# 17-RESET_GENERATION.net
KiCad netlist of a schematic drawn in Altium Designer
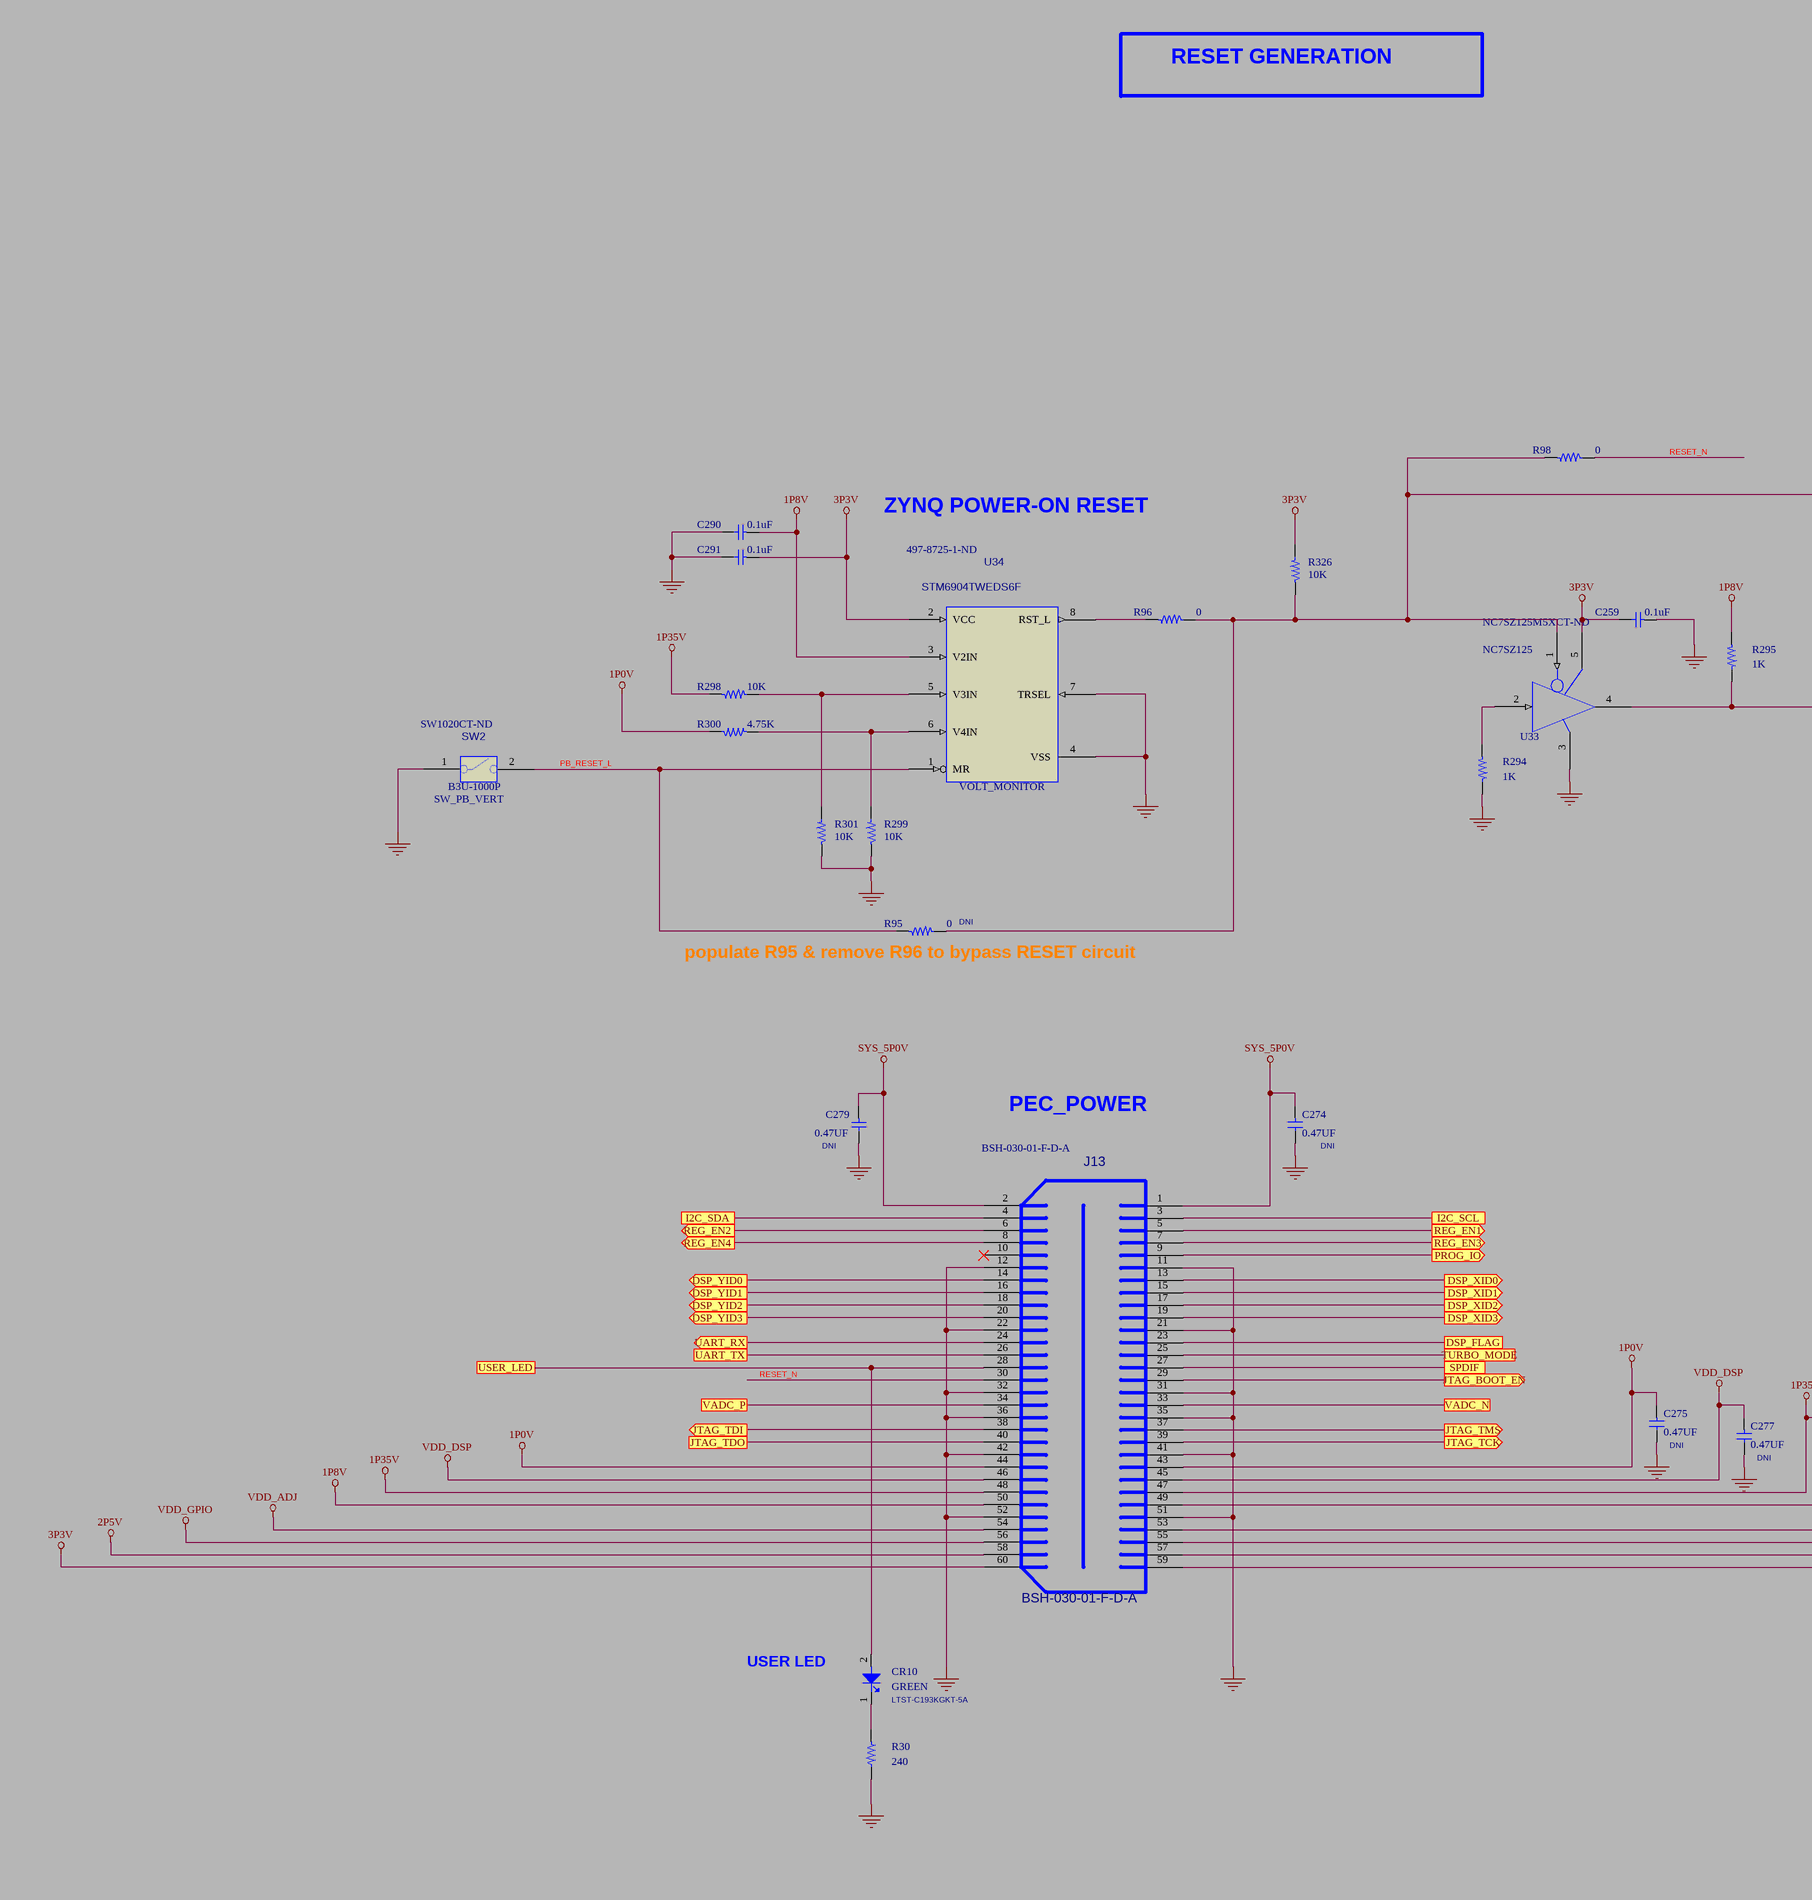
[diagram p0: 17-RESET GENERATION.SchDoc, left]
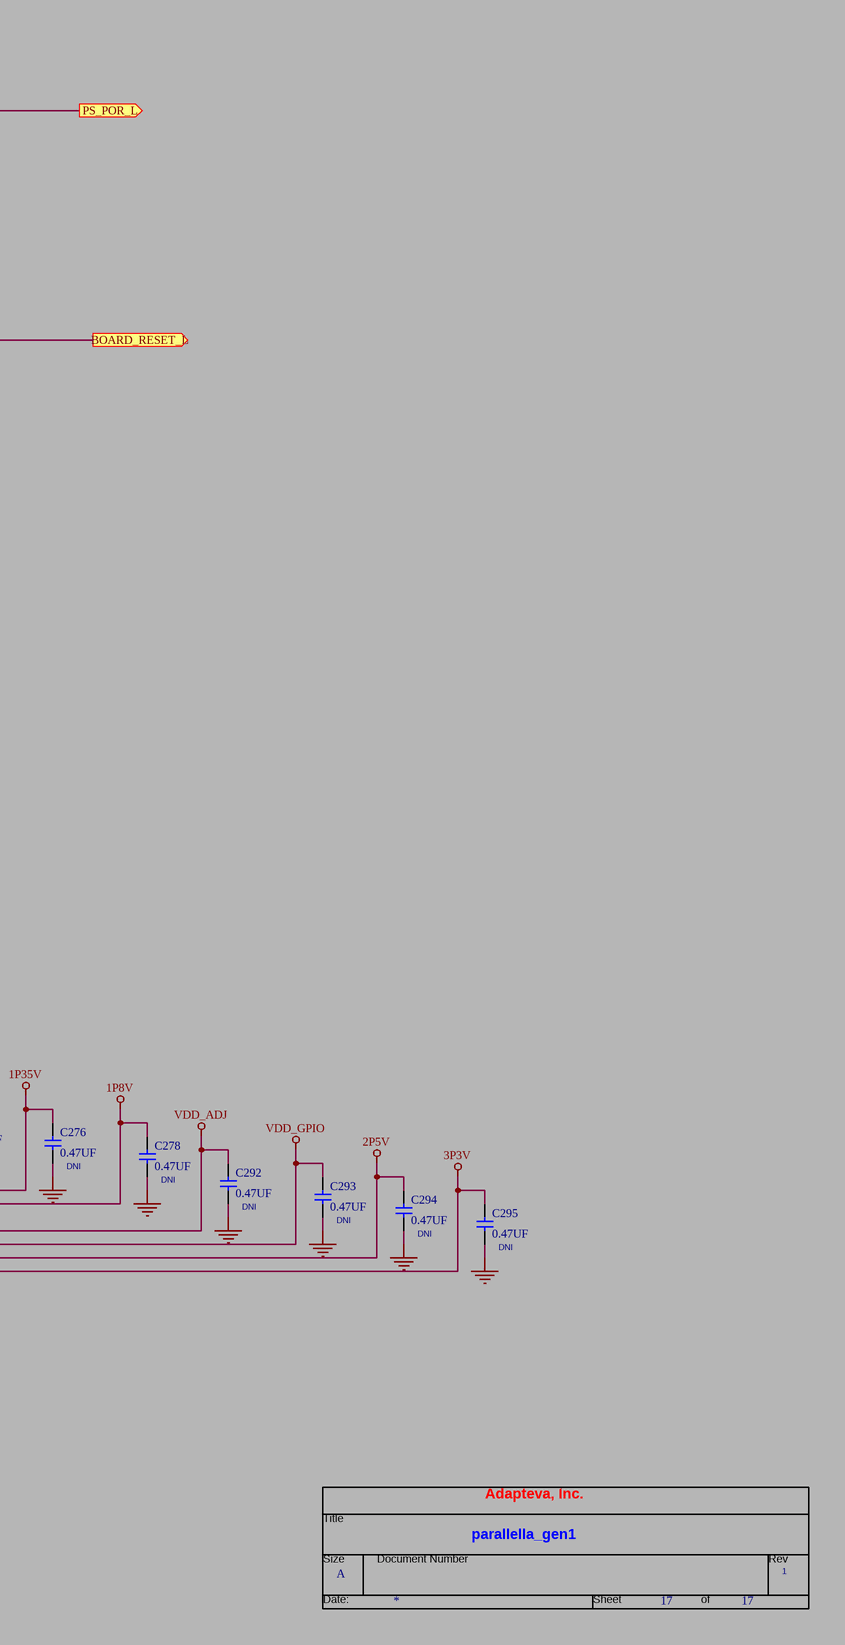
[diagram p1: 17-RESET GENERATION.SchDoc, right]

(export (version "E")
  (design (tool "Eeschema 10.0.6"))
  (components
    (comp (ref "C259")
      (value "0.1uF")
      (footprint "C0402")
      (description "CAP, 0402, 0.1UF, X5R, 35V")
      (fields (field (name "MFG PART NO") "GMK105BJ104KV-F") (field (name "MFG") "TAIYO YUDEN"))
      (libsource (lib "*") (part "CAP0402_0P1UF_X5R_35V"))
    )
    (comp (ref "C274")
      (value "0.47UF")
      (footprint "C0402")
      (description "CAP, 0402, 0.47UF, X5R, 16V")
      (fields
        (field (name "MFG") "TDK")
        (field (name "MFG PART NO") "C1005X5R1C474K")
        (field (name "INSTALL") "DNI")
      )
      (libsource (lib "*") (part "CAP0402_0P47UF_X5R"))
    )
    (comp (ref "C275")
      (value "0.47UF")
      (footprint "C0402")
      (description "CAP, 0402, 0.47UF, X5R, 16V")
      (fields
        (field (name "MFG") "TDK")
        (field (name "MFG PART NO") "C1005X5R1C474K")
        (field (name "INSTALL") "DNI")
      )
      (libsource (lib "*") (part "CAP0402_0P47UF_X5R"))
    )
    (comp (ref "C276")
      (value "0.47UF")
      (footprint "C0402")
      (description "CAP, 0402, 0.47UF, X5R, 16V")
      (fields
        (field (name "MFG") "TDK")
        (field (name "MFG PART NO") "C1005X5R1C474K")
        (field (name "INSTALL") "DNI")
      )
      (libsource (lib "*") (part "CAP0402_0P47UF_X5R"))
    )
    (comp (ref "C277")
      (value "0.47UF")
      (footprint "C0402")
      (description "CAP, 0402, 0.47UF, X5R, 16V")
      (fields
        (field (name "MFG") "TDK")
        (field (name "MFG PART NO") "C1005X5R1C474K")
        (field (name "INSTALL") "DNI")
      )
      (libsource (lib "*") (part "CAP0402_0P47UF_X5R"))
    )
    (comp (ref "C278")
      (value "0.47UF")
      (footprint "C0402")
      (description "CAP, 0402, 0.47UF, X5R, 16V")
      (fields
        (field (name "MFG") "TDK")
        (field (name "MFG PART NO") "C1005X5R1C474K")
        (field (name "INSTALL") "DNI")
      )
      (libsource (lib "*") (part "CAP0402_0P47UF_X5R"))
    )
    (comp (ref "C279")
      (value "0.47UF")
      (footprint "C0402")
      (description "CAP, 0402, 0.47UF, X5R, 16V")
      (fields
        (field (name "MFG") "TDK")
        (field (name "MFG PART NO") "C1005X5R1C474K")
        (field (name "INSTALL") "DNI")
      )
      (libsource (lib "*") (part "CAP0402_0P47UF_X5R"))
    )
    (comp (ref "C290")
      (value "0.1uF")
      (footprint "C0402")
      (description "CAP, 0402, 0.1UF, X5R, 35V")
      (fields (field (name "MFG PART NO") "GMK105BJ104KV-F") (field (name "MFG") "TAIYO YUDEN"))
      (libsource (lib "*") (part "CAP0402_0P1UF_X5R_35V"))
    )
    (comp (ref "C291")
      (value "0.1uF")
      (footprint "C0402")
      (description "CAP, 0402, 0.1UF, X5R, 35V")
      (fields (field (name "MFG PART NO") "GMK105BJ104KV-F") (field (name "MFG") "TAIYO YUDEN"))
      (libsource (lib "*") (part "CAP0402_0P1UF_X5R_35V"))
    )
    (comp (ref "C292")
      (value "0.47UF")
      (footprint "C0402")
      (description "CAP, 0402, 0.47UF, X5R, 16V")
      (fields
        (field (name "MFG") "TDK")
        (field (name "MFG PART NO") "C1005X5R1C474K")
        (field (name "INSTALL") "DNI")
      )
      (libsource (lib "*") (part "CAP0402_0P47UF_X5R"))
    )
    (comp (ref "C293")
      (value "0.47UF")
      (footprint "C0402")
      (description "CAP, 0402, 0.47UF, X5R, 16V")
      (fields
        (field (name "MFG") "TDK")
        (field (name "MFG PART NO") "C1005X5R1C474K")
        (field (name "INSTALL") "DNI")
      )
      (libsource (lib "*") (part "CAP0402_0P47UF_X5R"))
    )
    (comp (ref "C294")
      (value "0.47UF")
      (footprint "C0402")
      (description "CAP, 0402, 0.47UF, X5R, 16V")
      (fields
        (field (name "MFG") "TDK")
        (field (name "MFG PART NO") "C1005X5R1C474K")
        (field (name "INSTALL") "DNI")
      )
      (libsource (lib "*") (part "CAP0402_0P47UF_X5R"))
    )
    (comp (ref "C295")
      (value "0.47UF")
      (footprint "C0402")
      (description "CAP, 0402, 0.47UF, X5R, 16V")
      (fields
        (field (name "MFG") "TDK")
        (field (name "MFG PART NO") "C1005X5R1C474K")
        (field (name "INSTALL") "DNI")
      )
      (libsource (lib "*") (part "CAP0402_0P47UF_X5R"))
    )
    (comp (ref "CR10")
      (value "GREEN")
      (footprint "LED_0603")
      (description "LED, 0603, 5MA, SMT, GREEN")
      (fields
        (field (name "VOLTAGE") "2V")
        (field (name "MFG") "LITE-ON INC")
        (field (name "VENDOR PN") "LTST-C193KGKT-5A")
      )
      (libsource (lib "*") (part "LED_0603_5MA_GRN"))
    )
    (comp (ref "J13")
      (value "BSH-030-01-F-D-A")
      (footprint "CONN_BSH60P_13P59X25P88_P5P_V")
      (fields (field (name "SUPPLIER PART NUMBER 1") "BSH-030-01-F-D-A"))
      (libsource (lib "*") (part "CON_BSH_030_VERT"))
    )
    (comp (ref "R30")
      (value "240")
      (footprint "R0402")
      (description "RES, 0402, 240, 1%")
      (fields (field (name "MFG") "VISHAY") (field (name "MFG PART NO") "CRCW0402240RFKED"))
      (libsource (lib "*") (part "RES0402_240"))
    )
    (comp (ref "R95")
      (value "0")
      (footprint "R0402")
      (description "RES, 0402, 0 OHM, 1%")
      (fields
        (field (name "MFG") "VISHAY")
        (field (name "MFG PART NO") "CRCW04020000Z0ED")
        (field (name "INSTALL") "DNI")
      )
      (libsource (lib "*") (part "RES0402_0"))
    )
    (comp (ref "R96")
      (value "0")
      (footprint "R0402")
      (description "RES, 0402, 0 OHM, 1%")
      (fields (field (name "MFG") "VISHAY") (field (name "MFG PART NO") "CRCW04020000Z0ED"))
      (libsource (lib "*") (part "RES0402_0"))
    )
    (comp (ref "R98")
      (value "0")
      (footprint "R0402")
      (description "RES, 0402, 0 OHM, 1%")
      (fields (field (name "MFG") "VISHAY") (field (name "MFG PART NO") "CRCW04020000Z0ED"))
      (libsource (lib "*") (part "RES0402_0"))
    )
    (comp (ref "R294")
      (value "1K")
      (footprint "R0402")
      (description "RES, 0402, 1K")
      (fields (field (name "MFG") "VISHAY") (field (name "MFG PART NO") "CRCW04021K00FKED"))
      (libsource (lib "*") (part "RES0402_1K"))
    )
    (comp (ref "R295")
      (value "1K")
      (footprint "R0402")
      (description "RES, 0402, 1K")
      (fields (field (name "MFG") "VISHAY") (field (name "MFG PART NO") "CRCW04021K00FKED"))
      (libsource (lib "*") (part "RES0402_1K"))
    )
    (comp (ref "R298")
      (value "10K")
      (footprint "R0402")
      (description "RES, 0402, 10K")
      (fields (field (name "MFG") "VISHAY") (field (name "MFG PART NO") "CRCW040210K0FKED"))
      (libsource (lib "*") (part "RES0402_10K"))
    )
    (comp (ref "R299")
      (value "10K")
      (footprint "R0402")
      (description "RES, 0402, 10K")
      (fields (field (name "MFG") "VISHAY") (field (name "MFG PART NO") "CRCW040210K0FKED"))
      (libsource (lib "*") (part "RES0402_10K"))
    )
    (comp (ref "R300")
      (value "4.75K")
      (footprint "R0402")
      (description "RES, 0402, 4.75K, 1%")
      (fields (field (name "MFG") "VISHAY") (field (name "MFG PART NO") "CRCW04024K75FKED"))
      (libsource (lib "*") (part "RES0402_4K75"))
    )
    (comp (ref "R301")
      (value "10K")
      (footprint "R0402")
      (description "RES, 0402, 10K")
      (fields (field (name "MFG") "VISHAY") (field (name "MFG PART NO") "CRCW040210K0FKED"))
      (libsource (lib "*") (part "RES0402_10K"))
    )
    (comp (ref "R326")
      (value "10K")
      (footprint "R0402")
      (description "RES, 0402, 10K")
      (fields (field (name "MFG") "VISHAY") (field (name "MFG PART NO") "CRCW040210K0FKED"))
      (libsource (lib "*") (part "RES0402_10K"))
    )
    (comp (ref "SW2")
      (value "SW_PB_VERT")
      (footprint "SWITCH_2P5X4X1P6MMH")
      (description "SW, PUSHBUTTON, SPST, NORMALLY OPEN, SMT")
      (fields (field (name "VENDOR PN") "B3U-1000P") (field (name "SUPPLIER PART NUMBER 1") "SW1020CT-ND"))
      (libsource (lib "*") (part "SW_PB_SPST_2PIN"))
    )
    (comp (ref "U33")
      (value "NC7SZ125")
      (footprint "SOT_5PIN")
      (fields
        (field (name "PART_NUMBER") "XXX-XXXXX-XX")
        (field (name "MFG") "FAIRCHILD")
        (field (name "MFG PART NO") "NC7SZ125M5X")
        (field (name "SUPPLIER PART NUMBER 1") "NC7SZ125M5XCT-ND")
      )
      (libsource (lib "*") (part "NC7SZ125"))
    )
    (comp (ref "U34")
      (value "VOLT_MONITOR")
      (footprint "TSSOP8_3SQX1P1H_P65P")
      (description "IC,  SUPPLY MONITOR, 4 INPUTS, TSSOP8")
      (fields
        (field (name "MFG PART NO") "STM6904TWEDS6F")
        (field (name "MFG") "ST MICROELECTRONICS")
        (field (name "SUPPLIER PART NUMBER 1") "497-8725-1-ND")
      )
      (libsource (lib "*") (part "VOLTMON_4IN_3P3"))
    )
  )
  (nets
    (net (code "1") (name "/BOARD_RESET_L") (class "Default")
      (node (ref "R295") (pin "2") (pinfunction "2_2") (pintype "passive"))
      (node (ref "U33") (pin "4") (pinfunction "Y_4") (pintype "tri_state"))
    )
    (net (code "2") (name "/DSP_FLAG") (class "Default")
      (node (ref "J13") (pin "23") (pinfunction "23_23") (pintype "passive"))
    )
    (net (code "3") (name "/DSP_XID0") (class "Default")
      (node (ref "J13") (pin "13") (pinfunction "13_13") (pintype "passive"))
    )
    (net (code "4") (name "/DSP_XID1") (class "Default")
      (node (ref "J13") (pin "15") (pinfunction "15_15") (pintype "passive"))
    )
    (net (code "5") (name "/DSP_XID2") (class "Default")
      (node (ref "J13") (pin "17") (pinfunction "17_17") (pintype "passive"))
    )
    (net (code "6") (name "/DSP_XID3") (class "Default")
      (node (ref "J13") (pin "19") (pinfunction "19_19") (pintype "passive"))
    )
    (net (code "7") (name "/DSP_YID0") (class "Default")
      (node (ref "J13") (pin "14") (pinfunction "14_14") (pintype "passive"))
    )
    (net (code "8") (name "/DSP_YID1") (class "Default")
      (node (ref "J13") (pin "16") (pinfunction "16_16") (pintype "passive"))
    )
    (net (code "9") (name "/DSP_YID2") (class "Default")
      (node (ref "J13") (pin "18") (pinfunction "18_18") (pintype "passive"))
    )
    (net (code "10") (name "/DSP_YID3") (class "Default")
      (node (ref "J13") (pin "20") (pinfunction "20_20") (pintype "passive"))
    )
    (net (code "11") (name "/I2C_SCL") (class "Default")
      (node (ref "J13") (pin "3") (pinfunction "03_3") (pintype "passive"))
    )
    (net (code "12") (name "/I2C_SDA") (class "Default")
      (node (ref "J13") (pin "4") (pinfunction "04_4") (pintype "passive"))
    )
    (net (code "13") (name "/JTAG_BOOT_EN") (class "Default")
      (node (ref "J13") (pin "29") (pinfunction "29_29") (pintype "passive"))
    )
    (net (code "14") (name "/JTAG_TCK") (class "Default")
      (node (ref "J13") (pin "39") (pinfunction "39_39") (pintype "passive"))
    )
    (net (code "15") (name "/JTAG_TDI") (class "Default")
      (node (ref "J13") (pin "38") (pinfunction "38_38") (pintype "passive"))
    )
    (net (code "16") (name "/JTAG_TDO") (class "Default")
      (node (ref "J13") (pin "40") (pinfunction "40_40") (pintype "passive"))
    )
    (net (code "17") (name "/JTAG_TMS") (class "Default")
      (node (ref "J13") (pin "37") (pinfunction "37_37") (pintype "passive"))
    )
    (net (code "18") (name "/PB_RESET_L") (class "Default")
      (node (ref "R95") (pin "1") (pinfunction "1_1") (pintype "passive"))
      (node (ref "SW2") (pin "2") (pinfunction "B_2") (pintype "passive"))
      (node (ref "U34") (pin "1") (pinfunction "MR_1") (pintype "input"))
    )
    (net (code "19") (name "/PROG_IO") (class "Default")
      (node (ref "J13") (pin "9") (pinfunction "09_9") (pintype "passive"))
    )
    (net (code "20") (name "/PS_POR_L") (class "Default")
      (node (ref "R326") (pin "1") (pinfunction "1_1") (pintype "passive"))
      (node (ref "R95") (pin "2") (pinfunction "2_2") (pintype "passive"))
      (node (ref "R96") (pin "2") (pinfunction "2_2") (pintype "passive"))
      (node (ref "R98") (pin "1") (pinfunction "1_1") (pintype "passive"))
      (node (ref "U33") (pin "1") (pinfunction "~{OE}_1") (pintype "input"))
    )
    (net (code "21") (name "/REG_EN1") (class "Default")
      (node (ref "J13") (pin "5") (pinfunction "05_5") (pintype "passive"))
    )
    (net (code "22") (name "/REG_EN2") (class "Default")
      (node (ref "J13") (pin "6") (pinfunction "06_6") (pintype "passive"))
    )
    (net (code "23") (name "/REG_EN3") (class "Default")
      (node (ref "J13") (pin "7") (pinfunction "07_7") (pintype "passive"))
    )
    (net (code "24") (name "/REG_EN4") (class "Default")
      (node (ref "J13") (pin "8") (pinfunction "08_8") (pintype "passive"))
    )
    (net (code "25") (name "/RESET_N") (class "Default")
      (node (ref "J13") (pin "30") (pinfunction "30_30") (pintype "passive"))
      (node (ref "R98") (pin "2") (pinfunction "2_2") (pintype "passive"))
    )
    (net (code "26") (name "/SPDIF") (class "Default")
      (node (ref "J13") (pin "27") (pinfunction "27_27") (pintype "passive"))
    )
    (net (code "27") (name "/TURBO_MODE") (class "Default")
      (node (ref "J13") (pin "25") (pinfunction "25_25") (pintype "passive"))
    )
    (net (code "28") (name "/UART_RX") (class "Default")
      (node (ref "J13") (pin "24") (pinfunction "24_24") (pintype "passive"))
    )
    (net (code "29") (name "/UART_TX") (class "Default")
      (node (ref "J13") (pin "26") (pinfunction "26_26") (pintype "passive"))
    )
    (net (code "30") (name "/USER_LED") (class "Default")
      (node (ref "CR10") (pin "2") (pinfunction "A_2") (pintype "passive"))
      (node (ref "J13") (pin "28") (pinfunction "28_28") (pintype "passive"))
    )
    (net (code "31") (name "/VADC_N") (class "Default")
      (node (ref "J13") (pin "33") (pinfunction "33_33") (pintype "passive"))
    )
    (net (code "32") (name "/VADC_P") (class "Default")
      (node (ref "J13") (pin "34") (pinfunction "34_34") (pintype "passive"))
    )
    (net (code "33") (name "1P0V") (class "Default")
      (node (ref "C275") (pin "1") (pinfunction "1_1") (pintype "passive"))
      (node (ref "J13") (pin "43") (pinfunction "43_43") (pintype "passive"))
      (node (ref "J13") (pin "44") (pinfunction "44_44") (pintype "passive"))
      (node (ref "R300") (pin "2") (pinfunction "2_2") (pintype "passive"))
    )
    (net (code "34") (name "1P8V") (class "Default")
      (node (ref "C278") (pin "1") (pinfunction "1_1") (pintype "passive"))
      (node (ref "C290") (pin "1") (pinfunction "1_1") (pintype "passive"))
      (node (ref "J13") (pin "49") (pinfunction "49_49") (pintype "passive"))
      (node (ref "J13") (pin "50") (pinfunction "50_50") (pintype "passive"))
      (node (ref "R295") (pin "1") (pinfunction "1_1") (pintype "passive"))
      (node (ref "U34") (pin "3") (pinfunction "V2IN_3") (pintype "input"))
    )
    (net (code "35") (name "1P35V") (class "Default")
      (node (ref "C276") (pin "1") (pinfunction "1_1") (pintype "passive"))
      (node (ref "J13") (pin "47") (pinfunction "47_47") (pintype "passive"))
      (node (ref "J13") (pin "48") (pinfunction "48_48") (pintype "passive"))
      (node (ref "R298") (pin "1") (pinfunction "1_1") (pintype "passive"))
    )
    (net (code "36") (name "2P5V") (class "Default")
      (node (ref "C294") (pin "1") (pinfunction "1_1") (pintype "passive"))
      (node (ref "J13") (pin "57") (pinfunction "57_57") (pintype "passive"))
      (node (ref "J13") (pin "58") (pinfunction "58_58") (pintype "passive"))
    )
    (net (code "37") (name "3P3V") (class "Default")
      (node (ref "C259") (pin "2") (pinfunction "2_2") (pintype "passive"))
      (node (ref "C291") (pin "1") (pinfunction "1_1") (pintype "passive"))
      (node (ref "C295") (pin "1") (pinfunction "1_1") (pintype "passive"))
      (node (ref "J13") (pin "59") (pinfunction "59_59") (pintype "passive"))
      (node (ref "J13") (pin "60") (pinfunction "60_60") (pintype "passive"))
      (node (ref "R326") (pin "2") (pinfunction "2_2") (pintype "passive"))
      (node (ref "U33") (pin "5") (pinfunction "VCC_5") (pintype "passive"))
      (node (ref "U34") (pin "2") (pinfunction "VCC_2") (pintype "input"))
    )
    (net (code "38") (name "GND") (class "Default")
      (node (ref "C259") (pin "1") (pinfunction "1_1") (pintype "passive"))
      (node (ref "C274") (pin "2") (pinfunction "2_2") (pintype "passive"))
      (node (ref "C275") (pin "2") (pinfunction "2_2") (pintype "passive"))
      (node (ref "C276") (pin "2") (pinfunction "2_2") (pintype "passive"))
      (node (ref "C277") (pin "2") (pinfunction "2_2") (pintype "passive"))
      (node (ref "C278") (pin "2") (pinfunction "2_2") (pintype "passive"))
      (node (ref "C279") (pin "2") (pinfunction "2_2") (pintype "passive"))
      (node (ref "C290") (pin "2") (pinfunction "2_2") (pintype "passive"))
      (node (ref "C291") (pin "2") (pinfunction "2_2") (pintype "passive"))
      (node (ref "C292") (pin "2") (pinfunction "2_2") (pintype "passive"))
      (node (ref "C293") (pin "2") (pinfunction "2_2") (pintype "passive"))
      (node (ref "C294") (pin "2") (pinfunction "2_2") (pintype "passive"))
      (node (ref "C295") (pin "2") (pinfunction "2_2") (pintype "passive"))
      (node (ref "J13") (pin "11") (pinfunction "11_11") (pintype "passive"))
      (node (ref "J13") (pin "12") (pinfunction "12_12") (pintype "passive"))
      (node (ref "J13") (pin "21") (pinfunction "21_21") (pintype "passive"))
      (node (ref "J13") (pin "22") (pinfunction "22_22") (pintype "passive"))
      (node (ref "J13") (pin "31") (pinfunction "31_31") (pintype "passive"))
      (node (ref "J13") (pin "32") (pinfunction "32_32") (pintype "passive"))
      (node (ref "J13") (pin "35") (pinfunction "35_35") (pintype "passive"))
      (node (ref "J13") (pin "36") (pinfunction "36_36") (pintype "passive"))
      (node (ref "J13") (pin "41") (pinfunction "41_41") (pintype "passive"))
      (node (ref "J13") (pin "42") (pinfunction "42_42") (pintype "passive"))
      (node (ref "J13") (pin "51") (pinfunction "51_51") (pintype "passive"))
      (node (ref "J13") (pin "52") (pinfunction "52_52") (pintype "passive"))
      (node (ref "R294") (pin "2") (pinfunction "2_2") (pintype "passive"))
      (node (ref "R299") (pin "1") (pinfunction "1_1") (pintype "passive"))
      (node (ref "R30") (pin "2") (pinfunction "2_2") (pintype "passive"))
      (node (ref "R301") (pin "1") (pinfunction "1_1") (pintype "passive"))
      (node (ref "SW2") (pin "1") (pinfunction "A_1") (pintype "passive"))
      (node (ref "U33") (pin "3") (pinfunction "GND_3") (pintype "passive"))
      (node (ref "U34") (pin "4") (pinfunction "VSS_4") (pintype "power_in"))
      (node (ref "U34") (pin "7") (pinfunction "TRSEL_7") (pintype "input"))
    )
    (net (code "39") (name "Net-(CR10-C)") (class "Default")
      (node (ref "CR10") (pin "1") (pinfunction "C_1") (pintype "passive"))
      (node (ref "R30") (pin "1") (pinfunction "1_1") (pintype "passive"))
    )
    (net (code "40") (name "Net-(U33-A)") (class "Default")
      (node (ref "R294") (pin "1") (pinfunction "1_1") (pintype "passive"))
      (node (ref "U33") (pin "2") (pinfunction "A_2") (pintype "input"))
    )
    (net (code "41") (name "Net-(U34-RST_L)") (class "Default")
      (node (ref "R96") (pin "1") (pinfunction "1_1") (pintype "passive"))
      (node (ref "U34") (pin "8") (pinfunction "RST_L_8") (pintype "output"))
    )
    (net (code "42") (name "Net-(U34-V3IN)") (class "Default")
      (node (ref "R298") (pin "2") (pinfunction "2_2") (pintype "passive"))
      (node (ref "R301") (pin "2") (pinfunction "2_2") (pintype "passive"))
      (node (ref "U34") (pin "5") (pinfunction "V3IN_5") (pintype "input"))
    )
    (net (code "43") (name "Net-(U34-V4IN)") (class "Default")
      (node (ref "R299") (pin "2") (pinfunction "2_2") (pintype "passive"))
      (node (ref "R300") (pin "1") (pinfunction "1_1") (pintype "passive"))
      (node (ref "U34") (pin "6") (pinfunction "V4IN_6") (pintype "input"))
    )
    (net (code "44") (name "SYS_5P0V") (class "Default")
      (node (ref "C274") (pin "1") (pinfunction "1_1") (pintype "passive"))
      (node (ref "C279") (pin "1") (pinfunction "1_1") (pintype "passive"))
      (node (ref "J13") (pin "1") (pinfunction "01_1") (pintype "passive"))
      (node (ref "J13") (pin "2") (pinfunction "02_2") (pintype "passive"))
    )
    (net (code "45") (name "VDD_ADJ") (class "Default")
      (node (ref "C292") (pin "1") (pinfunction "1_1") (pintype "passive"))
      (node (ref "J13") (pin "53") (pinfunction "53_53") (pintype "passive"))
      (node (ref "J13") (pin "54") (pinfunction "54_54") (pintype "passive"))
    )
    (net (code "46") (name "VDD_DSP") (class "Default")
      (node (ref "C277") (pin "1") (pinfunction "1_1") (pintype "passive"))
      (node (ref "J13") (pin "45") (pinfunction "45_45") (pintype "passive"))
      (node (ref "J13") (pin "46") (pinfunction "46_46") (pintype "passive"))
    )
    (net (code "47") (name "VDD_GPIO") (class "Default")
      (node (ref "C293") (pin "1") (pinfunction "1_1") (pintype "passive"))
      (node (ref "J13") (pin "55") (pinfunction "55_55") (pintype "passive"))
      (node (ref "J13") (pin "56") (pinfunction "56_56") (pintype "passive"))
    )
    (net (code "48") (name "unconnected-(J13-Pad10)") (class "Default")
      (node (ref "J13") (pin "10") (pinfunction "10_10") (pintype "passive+no_connect"))
    )
  )
)
